# POWER.net
KiCad netlist of a schematic drawn in Altium Designer
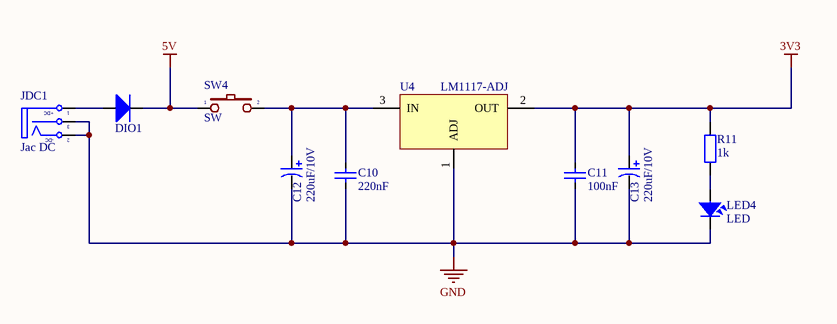
[diagram p0: POWER.SchDoc]

(export (version "E")
  (design (tool "Eeschema 10.0.6"))
  (components
    (comp (ref "C10")
      (value "220nF")
      (footprint "CAP_0805")
      (description "Capacitor")
      (fields (field (name "PUBLISHER") "Altium Limited"))
      (libsource (lib "My Library") (part "CapSMD"))
    )
    (comp (ref "C11")
      (value "100nF")
      (footprint "CAP_0805")
      (description "Capacitor")
      (fields (field (name "PUBLISHER") "Altium Limited"))
      (libsource (lib "My Library") (part "CapSMD"))
    )
    (comp (ref "C12")
      (value "220uF/10V")
      (footprint "CAP_7343")
      (description "Polazied Tantalum Capacitor")
      (libsource (lib "My Library") (part "CAP_TAN_SMD"))
    )
    (comp (ref "C13")
      (value "220uF/10V")
      (footprint "CAP_7343")
      (description "Polazied Tantalum Capacitor")
      (libsource (lib "My Library") (part "CAP_TAN_SMD"))
    )
    (comp (ref "DIO1")
      (value "Diode SMD")
      (footprint "DIO-214AC(SMA)")
      (description "Default Diode")
      (fields (field (name "PUBLISHER") "Altium Limited"))
      (libsource (lib "My Library") (part "Diode SMD"))
    )
    (comp (ref "JDC1")
      (value "Jac DC")
      (footprint "DC-IN")
      (description "Jac DC input")
      (libsource (lib "My Library") (part "DCIN"))
    )
    (comp (ref "LED4")
      (value "LED")
      (footprint "LED-0805-Red")
      (description "LED Single colour Green and Red")
      (libsource (lib "My Library") (part "LED"))
    )
    (comp (ref "R11")
      (value "1k")
      (footprint "RES-SMD-0805")
      (description "Resistor SMD")
      (fields
        (field (name "MANUFACTURER") "Generic Components")
        (field (name "PUBLISHER") "Altium Hobart Technology Centre")
      )
      (libsource (lib "My Library") (part "Resistor - SMD"))
    )
    (comp (ref "SW4")
      (value "SW")
      (footprint "SW2")
      (description "Switch button 2 pin")
      (libsource (lib "My Library") (part "SW2"))
    )
    (comp (ref "U4")
      (value "LM1117-ADJ")
      (footprint "LM1117-SOP")
      (description "800mA Low-Dropout Linear Regulator")
      (fields (field (name "CREATOR") "Nguyen Ba Bien"))
      (libsource (lib "My Library") (part "LM1117-ADJ"))
    )
  )
  (nets
    (net (code "1") (name "3V3") (class "Default")
      (node (ref "C11") (pin "2") (pinfunction "2_2") (pintype "passive"))
      (node (ref "C13") (pin "1") (pinfunction "1_1") (pintype "passive"))
      (node (ref "R11") (pin "1") (pinfunction "1_1") (pintype "passive"))
      (node (ref "U4") (pin "2") (pinfunction "OUT_2") (pintype "passive"))
    )
    (net (code "2") (name "5V") (class "Default")
      (node (ref "DIO1") (pin "2") (pinfunction "K_2") (pintype "passive"))
      (node (ref "SW4") (pin "1") (pinfunction "1_1") (pintype "passive"))
    )
    (net (code "3") (name "GND") (class "Default")
      (node (ref "C10") (pin "1") (pinfunction "1_1") (pintype "passive"))
      (node (ref "C11") (pin "1") (pinfunction "1_1") (pintype "passive"))
      (node (ref "C12") (pin "2") (pinfunction "2_2") (pintype "passive"))
      (node (ref "C13") (pin "2") (pinfunction "2_2") (pintype "passive"))
      (node (ref "JDC1") (pin "2") (pinfunction "TN_2") (pintype "passive"))
      (node (ref "JDC1") (pin "3") (pinfunction "S_3") (pintype "power_in"))
      (node (ref "LED4") (pin "2") (pinfunction "2_2") (pintype "passive"))
      (node (ref "U4") (pin "1") (pinfunction "ADJ_1") (pintype "passive"))
    )
    (net (code "4") (name "Net-(DIO1-A)") (class "Default")
      (node (ref "DIO1") (pin "1") (pinfunction "A_1") (pintype "passive"))
      (node (ref "JDC1") (pin "1") (pinfunction "T_1") (pintype "passive"))
    )
    (net (code "5") (name "Net-(LED4-Pad1)") (class "Default")
      (node (ref "LED4") (pin "1") (pinfunction "1_1") (pintype "passive"))
      (node (ref "R11") (pin "2") (pinfunction "2_2") (pintype "passive"))
    )
    (net (code "6") (name "Net-(U4-IN)") (class "Default")
      (node (ref "C10") (pin "2") (pinfunction "2_2") (pintype "passive"))
      (node (ref "C12") (pin "1") (pinfunction "1_1") (pintype "passive"))
      (node (ref "SW4") (pin "2") (pinfunction "2_2") (pintype "passive"))
      (node (ref "U4") (pin "3") (pinfunction "IN_3") (pintype "passive"))
    )
  )
)
